# Smartbox.net
KiCad netlist of a schematic drawn in EAGLE
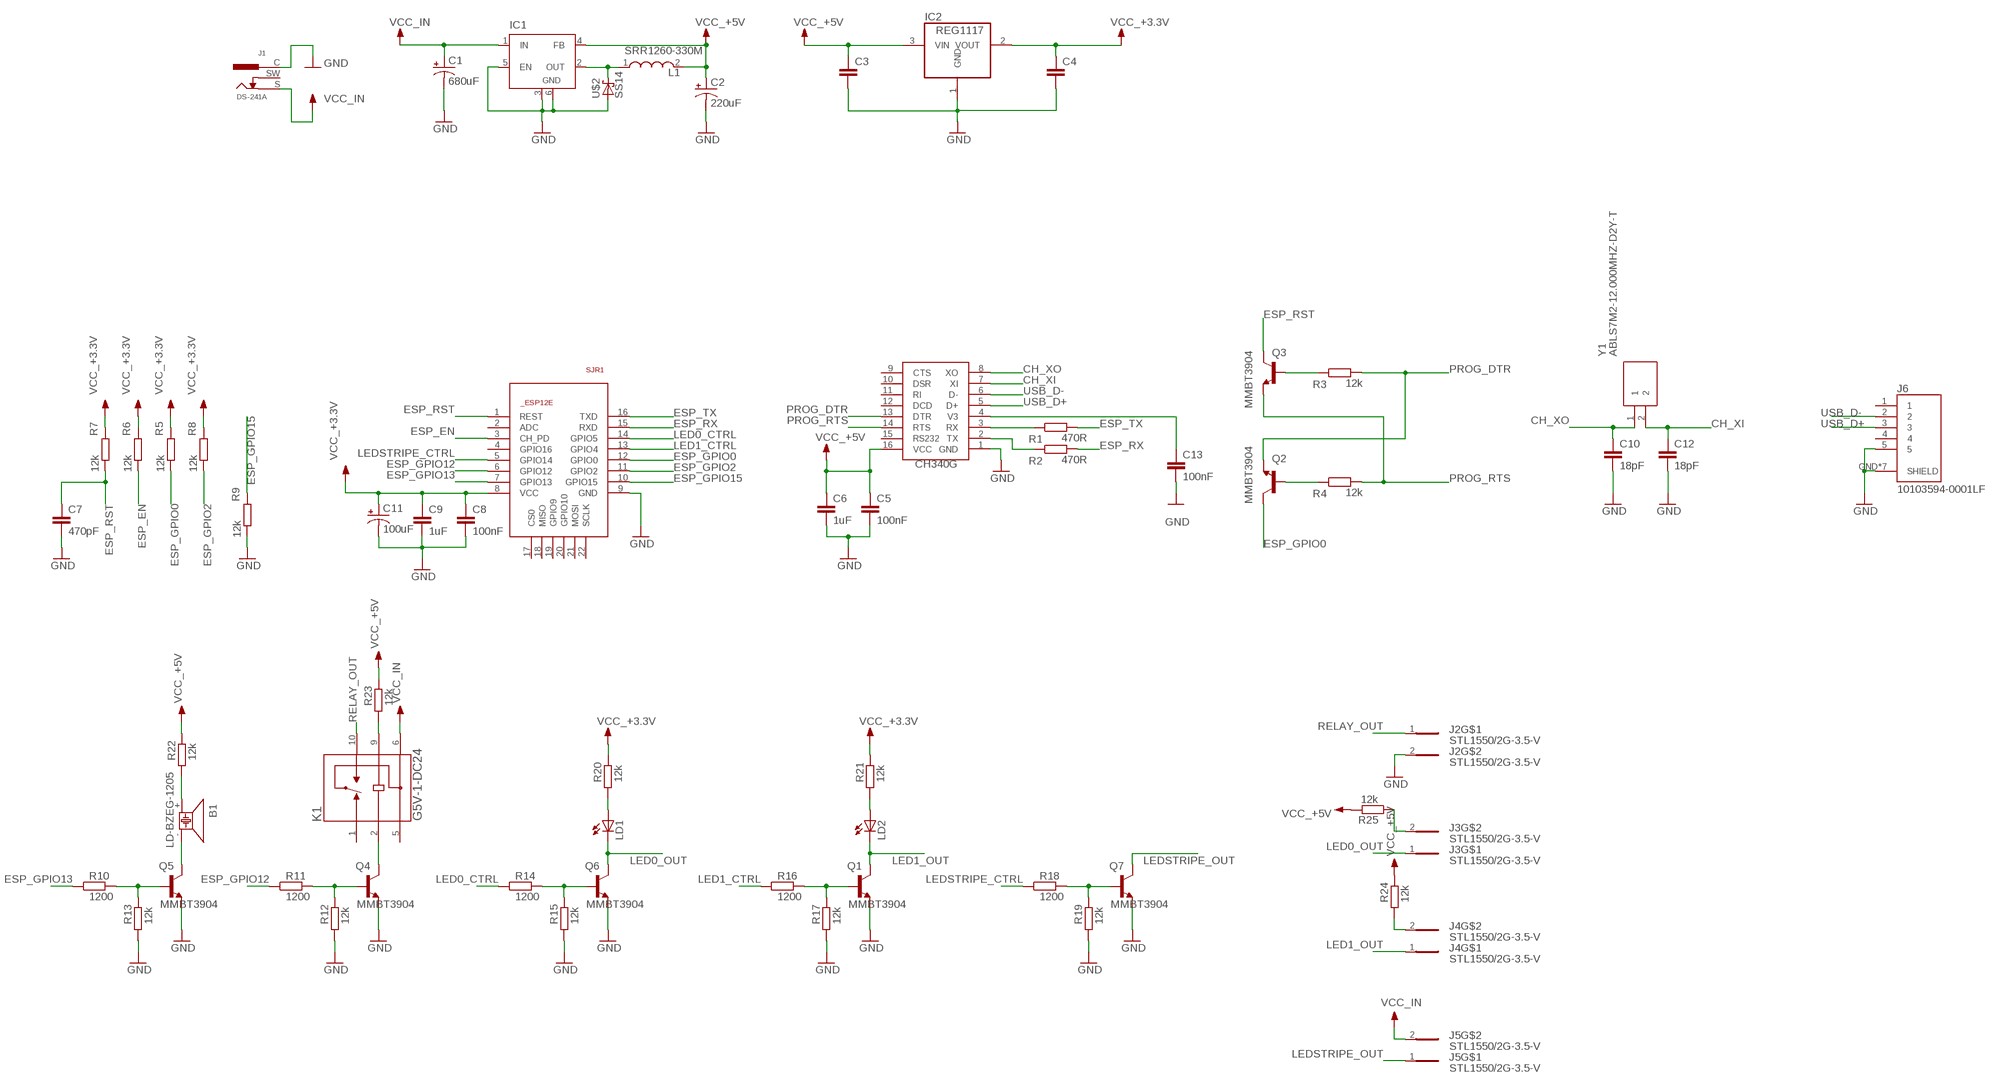
[diagram p0: schematic, sheet 1]

(export (version "E")
  (design (tool "Eeschema 10.0.6"))
  (components
    (comp (ref "B1")
      (value "LD-BZEG-1205")
      (footprint "eagle-import:LD-BZEG-12XX")
      (libsource (lib "eagle-import") (part "LD-BZEG-1205"))
    )
    (comp (ref "C1")
      (value "680uF")
      (footprint "eagle-import:PANASONIC_D")
      (libsource (lib "eagle-import") (part "100UF-POLAR-25V-20%(ELEC)"))
    )
    (comp (ref "C2")
      (value "220uF")
      (footprint "eagle-import:PANASONIC_D")
      (libsource (lib "eagle-import") (part "100UF-POLAR-25V-20%(ELEC)"))
    )
    (comp (ref "C3")
      (value "C-EUC0805")
      (footprint "eagle-import:C0805")
      (libsource (lib "eagle-import") (part "C-EUC0805"))
    )
    (comp (ref "C4")
      (value "C-EUC0805")
      (footprint "eagle-import:C0805")
      (libsource (lib "eagle-import") (part "C-EUC0805"))
    )
    (comp (ref "C5")
      (value "100nF")
      (footprint "eagle-import:C0805")
      (libsource (lib "eagle-import") (part "C-EUC0805"))
    )
    (comp (ref "C6")
      (value "1uF")
      (footprint "eagle-import:C0805")
      (libsource (lib "eagle-import") (part "C-EUC0805"))
    )
    (comp (ref "C7")
      (value "470pF")
      (footprint "eagle-import:C0805")
      (libsource (lib "eagle-import") (part "C-EUC0805"))
    )
    (comp (ref "C8")
      (value "100nF")
      (footprint "eagle-import:C0805")
      (libsource (lib "eagle-import") (part "C-EUC0805"))
    )
    (comp (ref "C9")
      (value "1uF")
      (footprint "eagle-import:C0805")
      (libsource (lib "eagle-import") (part "C-EUC0805"))
    )
    (comp (ref "C10")
      (value "18pF")
      (footprint "eagle-import:C0805")
      (libsource (lib "eagle-import") (part "C-EUC0805"))
    )
    (comp (ref "C11")
      (value "100uF")
      (footprint "eagle-import:PANASONIC_D")
      (libsource (lib "eagle-import") (part "100UF-POLAR-25V-20%(ELEC)"))
    )
    (comp (ref "C12")
      (value "18pF")
      (footprint "eagle-import:C0805")
      (libsource (lib "eagle-import") (part "C-EUC0805"))
    )
    (comp (ref "C13")
      (value "100nF")
      (footprint "eagle-import:C0805")
      (libsource (lib "eagle-import") (part "C-EUC0805"))
    )
    (comp (ref "IC1")
      (value "LM2596S")
      (footprint "eagle-import:TO263-5")
      (libsource (lib "eagle-import") (part "LM2596S"))
    )
    (comp (ref "IC2")
      (value "REG1117")
      (footprint "eagle-import:SOT223")
      (libsource (lib "eagle-import") (part "REG1117"))
    )
    (comp (ref "J1")
      (value "DS-241A")
      (footprint "eagle-import:DS-241")
      (libsource (lib "eagle-import") (part "DS-241A"))
    )
    (comp (ref "J2")
      (value "STL1550/2G-3.5-V")
      (footprint "eagle-import:STL1550_2G-3.5-V-GREEN")
      (libsource (lib "eagle-import") (part "STL1550/2G-3.5-V"))
    )
    (comp (ref "J3")
      (value "STL1550/2G-3.5-V")
      (footprint "eagle-import:STL1550_2G-3.5-V-GREEN")
      (libsource (lib "eagle-import") (part "STL1550/2G-3.5-V"))
    )
    (comp (ref "J4")
      (value "STL1550/2G-3.5-V")
      (footprint "eagle-import:STL1550_2G-3.5-V-GREEN")
      (libsource (lib "eagle-import") (part "STL1550/2G-3.5-V"))
    )
    (comp (ref "J5")
      (value "STL1550/2G-3.5-V")
      (footprint "eagle-import:STL1550_2G-3.5-V-GREEN")
      (libsource (lib "eagle-import") (part "STL1550/2G-3.5-V"))
    )
    (comp (ref "J6")
      (value "10103594-0001LF")
      (footprint "eagle-import:10103594-0001LF")
      (fields
        (field (name "DIGIKEY_PART_NUMBER") "609-4050-2-ND")
        (field (name "MANUFACTURER") "Amphenol ICC (FCI)")
        (field (name "CREATED_BY") "PCBLayout.com")
      )
      (libsource (lib "eagle-import") (part "10103594-0001LF"))
    )
    (comp (ref "K1")
      (value "G5V-1-DC24")
      (footprint "eagle-import:G5V-1-DC24")
      (fields
        (field (name "MANUFACTURER") "Omron Electronics Inc-EMC Div")
        (field (name "CREATED_BY") "  PCBLayout.com")
      )
      (libsource (lib "eagle-import") (part "G5V-1-DC24"))
    )
    (comp (ref "L1")
      (value "SRR1260-330M")
      (footprint "eagle-import:SRR1260-150M")
      (fields (field (name "MOUSER_PART_NUMBER") "652-SRR1260-330M"))
      (libsource (lib "eagle-import") (part "SRR1260-330M"))
    )
    (comp (ref "LD1")
      (value "LEDCHIPLED_0805")
      (footprint "eagle-import:CHIPLED_0805")
      (libsource (lib "eagle-import") (part "LEDCHIPLED_0805"))
    )
    (comp (ref "LD2")
      (value "LEDCHIPLED_0805")
      (footprint "eagle-import:CHIPLED_0805")
      (libsource (lib "eagle-import") (part "LEDCHIPLED_0805"))
    )
    (comp (ref "Q1")
      (value "MMBT3904")
      (footprint "eagle-import:SOT23")
      (fields
        (field (name "DIGIKEY_PART_NUMBER") "MMBT3904FSCT-ND")
        (field (name "MANUFACTURER") "ON Semiconductor")
        (field (name "CREATED_BY") "PCBLayout.com")
      )
      (libsource (lib "eagle-import") (part "MMBT3904"))
    )
    (comp (ref "Q2")
      (value "MMBT3904")
      (footprint "eagle-import:SOT23")
      (fields
        (field (name "DIGIKEY_PART_NUMBER") "MMBT3904FSCT-ND")
        (field (name "MANUFACTURER") "ON Semiconductor")
        (field (name "CREATED_BY") "PCBLayout.com")
      )
      (libsource (lib "eagle-import") (part "MMBT3904"))
    )
    (comp (ref "Q3")
      (value "MMBT3904")
      (footprint "eagle-import:SOT23")
      (fields
        (field (name "DIGIKEY_PART_NUMBER") "MMBT3904FSCT-ND")
        (field (name "MANUFACTURER") "ON Semiconductor")
        (field (name "CREATED_BY") "PCBLayout.com")
      )
      (libsource (lib "eagle-import") (part "MMBT3904"))
    )
    (comp (ref "Q4")
      (value "MMBT3904")
      (footprint "eagle-import:SOT23")
      (fields
        (field (name "DIGIKEY_PART_NUMBER") "MMBT3904FSCT-ND")
        (field (name "MANUFACTURER") "ON Semiconductor")
        (field (name "CREATED_BY") "PCBLayout.com")
      )
      (libsource (lib "eagle-import") (part "MMBT3904"))
    )
    (comp (ref "Q5")
      (value "MMBT3904")
      (footprint "eagle-import:SOT23")
      (fields
        (field (name "DIGIKEY_PART_NUMBER") "MMBT3904FSCT-ND")
        (field (name "MANUFACTURER") "ON Semiconductor")
        (field (name "CREATED_BY") "PCBLayout.com")
      )
      (libsource (lib "eagle-import") (part "MMBT3904"))
    )
    (comp (ref "Q6")
      (value "MMBT3904")
      (footprint "eagle-import:SOT23")
      (fields
        (field (name "DIGIKEY_PART_NUMBER") "MMBT3904FSCT-ND")
        (field (name "MANUFACTURER") "ON Semiconductor")
        (field (name "CREATED_BY") "PCBLayout.com")
      )
      (libsource (lib "eagle-import") (part "MMBT3904"))
    )
    (comp (ref "Q7")
      (value "MMBT3904")
      (footprint "eagle-import:SOT23")
      (fields
        (field (name "DIGIKEY_PART_NUMBER") "MMBT3904FSCT-ND")
        (field (name "MANUFACTURER") "ON Semiconductor")
        (field (name "CREATED_BY") "PCBLayout.com")
      )
      (libsource (lib "eagle-import") (part "MMBT3904"))
    )
    (comp (ref "R1")
      (value "470R")
      (footprint "eagle-import:R0805")
      (libsource (lib "eagle-import") (part "R-EU_R0805"))
    )
    (comp (ref "R2")
      (value "470R")
      (footprint "eagle-import:R0805")
      (libsource (lib "eagle-import") (part "R-EU_R0805"))
    )
    (comp (ref "R3")
      (value "12k")
      (footprint "eagle-import:R0805")
      (libsource (lib "eagle-import") (part "R-EU_R0805"))
    )
    (comp (ref "R4")
      (value "12k")
      (footprint "eagle-import:R0805")
      (libsource (lib "eagle-import") (part "R-EU_R0805"))
    )
    (comp (ref "R5")
      (value "12k")
      (footprint "eagle-import:R0805")
      (libsource (lib "eagle-import") (part "R-EU_R0805"))
    )
    (comp (ref "R6")
      (value "12k")
      (footprint "eagle-import:R0805")
      (libsource (lib "eagle-import") (part "R-EU_R0805"))
    )
    (comp (ref "R7")
      (value "12k")
      (footprint "eagle-import:R0805")
      (libsource (lib "eagle-import") (part "R-EU_R0805"))
    )
    (comp (ref "R8")
      (value "12k")
      (footprint "eagle-import:R0805")
      (libsource (lib "eagle-import") (part "R-EU_R0805"))
    )
    (comp (ref "R9")
      (value "12k")
      (footprint "eagle-import:R0805")
      (libsource (lib "eagle-import") (part "R-EU_R0805"))
    )
    (comp (ref "R10")
      (value "1200")
      (footprint "eagle-import:R0805")
      (libsource (lib "eagle-import") (part "R-EU_R0805"))
    )
    (comp (ref "R11")
      (value "1200")
      (footprint "eagle-import:R0805")
      (libsource (lib "eagle-import") (part "R-EU_R0805"))
    )
    (comp (ref "R12")
      (value "12k")
      (footprint "eagle-import:R0805")
      (libsource (lib "eagle-import") (part "R-EU_R0805"))
    )
    (comp (ref "R13")
      (value "12k")
      (footprint "eagle-import:R0805")
      (libsource (lib "eagle-import") (part "R-EU_R0805"))
    )
    (comp (ref "R14")
      (value "1200")
      (footprint "eagle-import:R0805")
      (libsource (lib "eagle-import") (part "R-EU_R0805"))
    )
    (comp (ref "R15")
      (value "12k")
      (footprint "eagle-import:R0805")
      (libsource (lib "eagle-import") (part "R-EU_R0805"))
    )
    (comp (ref "R16")
      (value "1200")
      (footprint "eagle-import:R0805")
      (libsource (lib "eagle-import") (part "R-EU_R0805"))
    )
    (comp (ref "R17")
      (value "12k")
      (footprint "eagle-import:R0805")
      (libsource (lib "eagle-import") (part "R-EU_R0805"))
    )
    (comp (ref "R18")
      (value "1200")
      (footprint "eagle-import:R0805")
      (libsource (lib "eagle-import") (part "R-EU_R0805"))
    )
    (comp (ref "R19")
      (value "12k")
      (footprint "eagle-import:R0805")
      (libsource (lib "eagle-import") (part "R-EU_R0805"))
    )
    (comp (ref "R20")
      (value "12k")
      (footprint "eagle-import:R0805")
      (libsource (lib "eagle-import") (part "R-EU_R0805"))
    )
    (comp (ref "R21")
      (value "12k")
      (footprint "eagle-import:R0805")
      (libsource (lib "eagle-import") (part "R-EU_R0805"))
    )
    (comp (ref "R22")
      (value "12k")
      (footprint "eagle-import:R0805")
      (libsource (lib "eagle-import") (part "R-EU_R0805"))
    )
    (comp (ref "R23")
      (value "12k")
      (footprint "eagle-import:R0805")
      (libsource (lib "eagle-import") (part "R-EU_R0805"))
    )
    (comp (ref "R24")
      (value "12k")
      (footprint "eagle-import:R0805")
      (libsource (lib "eagle-import") (part "R-EU_R0805"))
    )
    (comp (ref "R25")
      (value "12k")
      (footprint "eagle-import:R0805")
      (libsource (lib "eagle-import") (part "R-EU_R0805"))
    )
    (comp (ref "SJR1")
      (value "ESP8266-12EESP12E")
      (footprint "eagle-import:ESP8266-ESP12E")
      (libsource (lib "eagle-import") (part "ESP8266-12EESP12E"))
    )
    (comp (ref "U$2")
      (value "SS14")
      (footprint "eagle-import:DO-214AC")
      (fields (field (name "MF") "ON Semiconductor"))
      (libsource (lib "eagle-import") (part "SS14"))
    )
    (comp (ref "U$3")
      (value "CH340G")
      (footprint "eagle-import:SOIC16")
      (libsource (lib "eagle-import") (part "CH340G"))
    )
    (comp (ref "Y1")
      (value "ABLS7M2-12.000MHZ-D2Y-T")
      (footprint "eagle-import:ABLS7M216000MHZD2YT")
      (fields
        (field (name "MANUFACTURER_PART_NUMBER") "ABLS7M2-16.000MHZ-D2Y-T")
        (field (name "MOUSER_PART_NUMBER") "815-ABLS7M216MHZD2YT")
      )
      (libsource (lib "eagle-import") (part "ABLS7M2-16.000MHZ-D2Y-T"))
    )
  )
  (nets
    (net (code "1") (name "/CH_XI") (class "Default")
      (node (ref "C12") (pin "1") (pinfunction "1_1") (pintype "passive"))
      (node (ref "U$3") (pin "7") (pinfunction "XI_7") (pintype "bidirectional"))
      (node (ref "Y1") (pin "2") (pinfunction "2_2") (pintype "bidirectional"))
    )
    (net (code "2") (name "/CH_XO") (class "Default")
      (node (ref "C10") (pin "1") (pinfunction "1_1") (pintype "passive"))
      (node (ref "U$3") (pin "8") (pinfunction "XO_8") (pintype "bidirectional"))
      (node (ref "Y1") (pin "1") (pinfunction "1_1") (pintype "bidirectional"))
    )
    (net (code "3") (name "/ESP_EN") (class "Default")
      (node (ref "R6") (pin "2") (pinfunction "2_2") (pintype "passive"))
      (node (ref "SJR1") (pin "3") (pinfunction "CH_PD_3") (pintype "bidirectional"))
    )
    (net (code "4") (name "/ESP_GPIO0") (class "Default")
      (node (ref "Q2") (pin "3") (pinfunction "C_3") (pintype "passive"))
      (node (ref "R5") (pin "2") (pinfunction "2_2") (pintype "passive"))
      (node (ref "SJR1") (pin "12") (pinfunction "GPIO0_12") (pintype "bidirectional"))
    )
    (net (code "5") (name "/ESP_GPIO2") (class "Default")
      (node (ref "R8") (pin "2") (pinfunction "2_2") (pintype "passive"))
      (node (ref "SJR1") (pin "11") (pinfunction "GPIO2_11") (pintype "bidirectional"))
    )
    (net (code "6") (name "/ESP_GPIO12") (class "Default")
      (node (ref "R11") (pin "1") (pinfunction "1_1") (pintype "passive"))
      (node (ref "SJR1") (pin "6") (pinfunction "GPIO12_6") (pintype "bidirectional"))
    )
    (net (code "7") (name "/ESP_GPIO13") (class "Default")
      (node (ref "R10") (pin "1") (pinfunction "1_1") (pintype "passive"))
      (node (ref "SJR1") (pin "7") (pinfunction "GPIO13_7") (pintype "bidirectional"))
    )
    (net (code "8") (name "/ESP_GPIO15") (class "Default")
      (node (ref "R9") (pin "1") (pinfunction "1_1") (pintype "passive"))
      (node (ref "SJR1") (pin "10") (pinfunction "GPIO15_10") (pintype "bidirectional"))
    )
    (net (code "9") (name "/ESP_RST") (class "Default")
      (node (ref "C7") (pin "1") (pinfunction "1_1") (pintype "passive"))
      (node (ref "Q3") (pin "3") (pinfunction "C_3") (pintype "passive"))
      (node (ref "R7") (pin "2") (pinfunction "2_2") (pintype "passive"))
      (node (ref "SJR1") (pin "1") (pinfunction "REST_1") (pintype "bidirectional"))
    )
    (net (code "10") (name "/ESP_RX") (class "Default")
      (node (ref "R2") (pin "2") (pinfunction "2_2") (pintype "passive"))
      (node (ref "SJR1") (pin "15") (pinfunction "RXD_15") (pintype "bidirectional"))
    )
    (net (code "11") (name "/ESP_TX") (class "Default")
      (node (ref "R1") (pin "2") (pinfunction "2_2") (pintype "passive"))
      (node (ref "SJR1") (pin "16") (pinfunction "TXD_16") (pintype "bidirectional"))
    )
    (net (code "12") (name "/LED0_CTRL") (class "Default")
      (node (ref "R14") (pin "1") (pinfunction "1_1") (pintype "passive"))
      (node (ref "SJR1") (pin "14") (pinfunction "GPIO5_14") (pintype "bidirectional"))
    )
    (net (code "13") (name "/LED0_OUT") (class "Default")
      (node (ref "J3") (pin "1") (pinfunction "1_1") (pintype "passive"))
      (node (ref "LD1") (pin "C") (pinfunction "C_C") (pintype "passive"))
      (node (ref "Q6") (pin "3") (pinfunction "C_3") (pintype "passive"))
    )
    (net (code "14") (name "/LED1_CTRL") (class "Default")
      (node (ref "R16") (pin "1") (pinfunction "1_1") (pintype "passive"))
      (node (ref "SJR1") (pin "13") (pinfunction "GPIO4_13") (pintype "bidirectional"))
    )
    (net (code "15") (name "/LED1_OUT") (class "Default")
      (node (ref "J4") (pin "1") (pinfunction "1_1") (pintype "passive"))
      (node (ref "LD2") (pin "C") (pinfunction "C_C") (pintype "passive"))
      (node (ref "Q1") (pin "3") (pinfunction "C_3") (pintype "passive"))
    )
    (net (code "16") (name "/LEDSTRIPE_CTRL") (class "Default")
      (node (ref "R18") (pin "1") (pinfunction "1_1") (pintype "passive"))
      (node (ref "SJR1") (pin "5") (pinfunction "GPIO14_5") (pintype "bidirectional"))
    )
    (net (code "17") (name "/LEDSTRIPE_OUT") (class "Default")
      (node (ref "J5") (pin "1") (pinfunction "1_1") (pintype "passive"))
      (node (ref "Q7") (pin "3") (pinfunction "C_3") (pintype "passive"))
    )
    (net (code "18") (name "/PROG_DTR") (class "Default")
      (node (ref "Q2") (pin "2") (pinfunction "E_2") (pintype "passive"))
      (node (ref "R3") (pin "2") (pinfunction "2_2") (pintype "passive"))
      (node (ref "U$3") (pin "13") (pinfunction "DTR_13") (pintype "bidirectional"))
    )
    (net (code "19") (name "/PROG_RTS") (class "Default")
      (node (ref "Q3") (pin "2") (pinfunction "E_2") (pintype "passive"))
      (node (ref "R4") (pin "2") (pinfunction "2_2") (pintype "passive"))
      (node (ref "U$3") (pin "14") (pinfunction "RTS_14") (pintype "bidirectional"))
    )
    (net (code "20") (name "/RELAY_OUT") (class "Default")
      (node (ref "J2") (pin "1") (pinfunction "1_1") (pintype "passive"))
      (node (ref "K1") (pin "10") (pinfunction "10_10") (pintype "passive"))
    )
    (net (code "21") (name "/USB_D+") (class "Default")
      (node (ref "J6") (pin "3") (pinfunction "3_3") (pintype "passive"))
      (node (ref "U$3") (pin "5") (pinfunction "D+_5") (pintype "bidirectional"))
    )
    (net (code "22") (name "/USB_D-") (class "Default")
      (node (ref "J6") (pin "2") (pinfunction "2_2") (pintype "passive"))
      (node (ref "U$3") (pin "6") (pinfunction "D-_6") (pintype "bidirectional"))
    )
    (net (code "23") (name "GND") (class "Default")
      (node (ref "C1") (pin "-") (pinfunction "-_-") (pintype "passive"))
      (node (ref "C10") (pin "2") (pinfunction "2_2") (pintype "passive"))
      (node (ref "C11") (pin "-") (pinfunction "-_-") (pintype "passive"))
      (node (ref "C12") (pin "2") (pinfunction "2_2") (pintype "passive"))
      (node (ref "C13") (pin "1") (pinfunction "1_1") (pintype "passive"))
      (node (ref "C2") (pin "-") (pinfunction "-_-") (pintype "passive"))
      (node (ref "C3") (pin "2") (pinfunction "2_2") (pintype "passive"))
      (node (ref "C4") (pin "2") (pinfunction "2_2") (pintype "passive"))
      (node (ref "C5") (pin "2") (pinfunction "2_2") (pintype "passive"))
      (node (ref "C6") (pin "2") (pinfunction "2_2") (pintype "passive"))
      (node (ref "C7") (pin "2") (pinfunction "2_2") (pintype "passive"))
      (node (ref "C8") (pin "2") (pinfunction "2_2") (pintype "passive"))
      (node (ref "C9") (pin "2") (pinfunction "2_2") (pintype "passive"))
      (node (ref "IC1") (pin "3") (pinfunction "GND_3") (pintype "power_in"))
      (node (ref "IC1") (pin "5") (pinfunction "EN_5") (pintype "input"))
      (node (ref "IC1") (pin "6") (pinfunction "GND_6") (pintype "power_in"))
      (node (ref "IC2") (pin "1") (pinfunction "GND_1") (pintype "power_in"))
      (node (ref "J1") (pin "C") (pinfunction "C_C") (pintype "passive"))
      (node (ref "J2") (pin "2") (pinfunction "1_2") (pintype "passive"))
      (node (ref "J6") (pin "5") (pinfunction "5_5") (pintype "passive"))
      (node (ref "J6") (pin "GND") (pinfunction "SHIELD_GND") (pintype "passive"))
      (node (ref "J6") (pin "GND$1") (pinfunction "SHIELD_GND$1") (pintype "passive"))
      (node (ref "J6") (pin "GND$2") (pinfunction "SHIELD_GND$2") (pintype "passive"))
      (node (ref "J6") (pin "S1") (pinfunction "SHIELD_S1") (pintype "passive"))
      (node (ref "J6") (pin "S2") (pinfunction "SHIELD_S2") (pintype "passive"))
      (node (ref "J6") (pin "S3") (pinfunction "SHIELD_S3") (pintype "passive"))
      (node (ref "J6") (pin "S4") (pinfunction "SHIELD_S4") (pintype "passive"))
      (node (ref "Q1") (pin "2") (pinfunction "E_2") (pintype "passive"))
      (node (ref "Q4") (pin "2") (pinfunction "E_2") (pintype "passive"))
      (node (ref "Q5") (pin "2") (pinfunction "E_2") (pintype "passive"))
      (node (ref "Q6") (pin "2") (pinfunction "E_2") (pintype "passive"))
      (node (ref "Q7") (pin "2") (pinfunction "E_2") (pintype "passive"))
      (node (ref "R12") (pin "1") (pinfunction "1_1") (pintype "passive"))
      (node (ref "R13") (pin "1") (pinfunction "1_1") (pintype "passive"))
      (node (ref "R15") (pin "1") (pinfunction "1_1") (pintype "passive"))
      (node (ref "R17") (pin "1") (pinfunction "1_1") (pintype "passive"))
      (node (ref "R19") (pin "1") (pinfunction "1_1") (pintype "passive"))
      (node (ref "R9") (pin "2") (pinfunction "2_2") (pintype "passive"))
      (node (ref "SJR1") (pin "9") (pinfunction "GND_9") (pintype "bidirectional"))
      (node (ref "U$2") (pin "A") (pinfunction "A_A") (pintype "passive"))
      (node (ref "U$3") (pin "1") (pinfunction "GND_1") (pintype "bidirectional"))
    )
    (net (code "24") (name "Net-(B1-Pad+)") (class "Default")
      (node (ref "B1") (pin "+") (pinfunction "+_+") (pintype "passive"))
      (node (ref "R22") (pin "1") (pinfunction "1_1") (pintype "passive"))
    )
    (net (code "25") (name "Net-(IC1-OUT)") (class "Default")
      (node (ref "IC1") (pin "2") (pinfunction "OUT_2") (pintype "output"))
      (node (ref "L1") (pin "1") (pinfunction "1_1") (pintype "bidirectional"))
      (node (ref "U$2") (pin "C") (pinfunction "C_C") (pintype "passive"))
    )
    (net (code "26") (name "Net-(J3B-1)") (class "Default")
      (node (ref "J3") (pin "2") (pinfunction "1_2") (pintype "passive"))
      (node (ref "R25") (pin "1") (pinfunction "1_1") (pintype "passive"))
    )
    (net (code "27") (name "Net-(J4B-1)") (class "Default")
      (node (ref "J4") (pin "2") (pinfunction "1_2") (pintype "passive"))
      (node (ref "R24") (pin "1") (pinfunction "1_1") (pintype "passive"))
    )
    (net (code "28") (name "Net-(K1-Pad9)") (class "Default")
      (node (ref "K1") (pin "9") (pinfunction "9_9") (pintype "passive"))
      (node (ref "R23") (pin "1") (pinfunction "1_1") (pintype "passive"))
    )
    (net (code "29") (name "Net-(LD1-PadA)") (class "Default")
      (node (ref "LD1") (pin "A") (pinfunction "A_A") (pintype "passive"))
      (node (ref "R20") (pin "1") (pinfunction "1_1") (pintype "passive"))
    )
    (net (code "30") (name "Net-(LD2-PadA)") (class "Default")
      (node (ref "LD2") (pin "A") (pinfunction "A_A") (pintype "passive"))
      (node (ref "R21") (pin "1") (pinfunction "1_1") (pintype "passive"))
    )
    (net (code "31") (name "Net-(Q1-B)") (class "Default")
      (node (ref "Q1") (pin "1") (pinfunction "B_1") (pintype "passive"))
      (node (ref "R16") (pin "2") (pinfunction "2_2") (pintype "passive"))
      (node (ref "R17") (pin "2") (pinfunction "2_2") (pintype "passive"))
    )
    (net (code "32") (name "Net-(Q2-B)") (class "Default")
      (node (ref "Q2") (pin "1") (pinfunction "B_1") (pintype "passive"))
      (node (ref "R4") (pin "1") (pinfunction "1_1") (pintype "passive"))
    )
    (net (code "33") (name "Net-(Q3-B)") (class "Default")
      (node (ref "Q3") (pin "1") (pinfunction "B_1") (pintype "passive"))
      (node (ref "R3") (pin "1") (pinfunction "1_1") (pintype "passive"))
    )
    (net (code "34") (name "Net-(Q4-B)") (class "Default")
      (node (ref "Q4") (pin "1") (pinfunction "B_1") (pintype "passive"))
      (node (ref "R11") (pin "2") (pinfunction "2_2") (pintype "passive"))
      (node (ref "R12") (pin "2") (pinfunction "2_2") (pintype "passive"))
    )
    (net (code "35") (name "Net-(Q4-C)") (class "Default")
      (node (ref "K1") (pin "2") (pinfunction "2_2") (pintype "passive"))
      (node (ref "Q4") (pin "3") (pinfunction "C_3") (pintype "passive"))
    )
    (net (code "36") (name "Net-(Q5-B)") (class "Default")
      (node (ref "Q5") (pin "1") (pinfunction "B_1") (pintype "passive"))
      (node (ref "R10") (pin "2") (pinfunction "2_2") (pintype "passive"))
      (node (ref "R13") (pin "2") (pinfunction "2_2") (pintype "passive"))
    )
    (net (code "37") (name "Net-(Q5-C)") (class "Default")
      (node (ref "B1") (pin "-") (pinfunction "-_-") (pintype "passive"))
      (node (ref "Q5") (pin "3") (pinfunction "C_3") (pintype "passive"))
    )
    (net (code "38") (name "Net-(Q6-B)") (class "Default")
      (node (ref "Q6") (pin "1") (pinfunction "B_1") (pintype "passive"))
      (node (ref "R14") (pin "2") (pinfunction "2_2") (pintype "passive"))
      (node (ref "R15") (pin "2") (pinfunction "2_2") (pintype "passive"))
    )
    (net (code "39") (name "Net-(Q7-B)") (class "Default")
      (node (ref "Q7") (pin "1") (pinfunction "B_1") (pintype "passive"))
      (node (ref "R18") (pin "2") (pinfunction "2_2") (pintype "passive"))
      (node (ref "R19") (pin "2") (pinfunction "2_2") (pintype "passive"))
    )
    (net (code "40") (name "Net-(U$3-RX)") (class "Default")
      (node (ref "R1") (pin "1") (pinfunction "1_1") (pintype "passive"))
      (node (ref "U$3") (pin "3") (pinfunction "RX_3") (pintype "bidirectional"))
    )
    (net (code "41") (name "Net-(U$3-TX)") (class "Default")
      (node (ref "R2") (pin "1") (pinfunction "1_1") (pintype "passive"))
      (node (ref "U$3") (pin "2") (pinfunction "TX_2") (pintype "bidirectional"))
    )
    (net (code "42") (name "Net-(U$3-V3)") (class "Default")
      (node (ref "C13") (pin "2") (pinfunction "2_2") (pintype "passive"))
      (node (ref "U$3") (pin "4") (pinfunction "V3_4") (pintype "bidirectional"))
    )
    (net (code "43") (name "VCC_+3.3V") (class "Default")
      (node (ref "C11") (pin "+") (pinfunction "+_+") (pintype "passive"))
      (node (ref "C4") (pin "1") (pinfunction "1_1") (pintype "passive"))
      (node (ref "C8") (pin "1") (pinfunction "1_1") (pintype "passive"))
      (node (ref "C9") (pin "1") (pinfunction "1_1") (pintype "passive"))
      (node (ref "IC2") (pin "2") (pinfunction "VOUT_2") (pintype "output"))
      (node (ref "R20") (pin "2") (pinfunction "2_2") (pintype "passive"))
      (node (ref "R21") (pin "2") (pinfunction "2_2") (pintype "passive"))
      (node (ref "R5") (pin "1") (pinfunction "1_1") (pintype "passive"))
      (node (ref "R6") (pin "1") (pinfunction "1_1") (pintype "passive"))
      (node (ref "R7") (pin "1") (pinfunction "1_1") (pintype "passive"))
      (node (ref "R8") (pin "1") (pinfunction "1_1") (pintype "passive"))
      (node (ref "SJR1") (pin "8") (pinfunction "VCC_8") (pintype "bidirectional"))
    )
    (net (code "44") (name "VCC_+5V") (class "Default")
      (node (ref "C2") (pin "+") (pinfunction "+_+") (pintype "passive"))
      (node (ref "C3") (pin "1") (pinfunction "1_1") (pintype "passive"))
      (node (ref "C5") (pin "1") (pinfunction "1_1") (pintype "passive"))
      (node (ref "C6") (pin "1") (pinfunction "1_1") (pintype "passive"))
      (node (ref "IC1") (pin "4") (pinfunction "FB_4") (pintype "input"))
      (node (ref "IC2") (pin "3") (pinfunction "VIN_3") (pintype "input"))
      (node (ref "L1") (pin "2") (pinfunction "2_2") (pintype "bidirectional"))
      (node (ref "R22") (pin "2") (pinfunction "2_2") (pintype "passive"))
      (node (ref "R23") (pin "2") (pinfunction "2_2") (pintype "passive"))
      (node (ref "R24") (pin "2") (pinfunction "2_2") (pintype "passive"))
      (node (ref "R25") (pin "2") (pinfunction "2_2") (pintype "passive"))
      (node (ref "U$3") (pin "16") (pinfunction "VCC_16") (pintype "bidirectional"))
    )
    (net (code "45") (name "VCC_IN") (class "Default")
      (node (ref "C1") (pin "+") (pinfunction "+_+") (pintype "passive"))
      (node (ref "IC1") (pin "1") (pinfunction "IN_1") (pintype "input"))
      (node (ref "J1") (pin "S") (pinfunction "S_S") (pintype "passive"))
      (node (ref "J5") (pin "2") (pinfunction "1_2") (pintype "passive"))
      (node (ref "K1") (pin "6") (pinfunction "6_6") (pintype "passive"))
    )
    (net (code "46") (name "unconnected-(J1-PadSW)") (class "Default")
      (node (ref "J1") (pin "SW") (pinfunction "SW_SW") (pintype "passive"))
    )
    (net (code "47") (name "unconnected-(J6-Pad1)") (class "Default")
      (node (ref "J6") (pin "1") (pinfunction "1_1") (pintype "passive"))
    )
    (net (code "48") (name "unconnected-(J6-Pad4)") (class "Default")
      (node (ref "J6") (pin "4") (pinfunction "4_4") (pintype "passive"))
    )
    (net (code "49") (name "unconnected-(K1-Pad1)") (class "Default")
      (node (ref "K1") (pin "1") (pinfunction "1_1") (pintype "passive"))
    )
    (net (code "50") (name "unconnected-(K1-Pad5)") (class "Default")
      (node (ref "K1") (pin "5") (pinfunction "5_5") (pintype "passive"))
    )
    (net (code "51") (name "unconnected-(SJR1-ADC-Pad2)") (class "Default")
      (node (ref "SJR1") (pin "2") (pinfunction "ADC_2") (pintype "bidirectional"))
    )
    (net (code "52") (name "unconnected-(SJR1-CS0-Pad17)") (class "Default")
      (node (ref "SJR1") (pin "17") (pinfunction "CS0_17") (pintype "bidirectional"))
    )
    (net (code "53") (name "unconnected-(SJR1-GPIO9-Pad19)") (class "Default")
      (node (ref "SJR1") (pin "19") (pinfunction "GPIO9_19") (pintype "bidirectional"))
    )
    (net (code "54") (name "unconnected-(SJR1-GPIO10-Pad20)") (class "Default")
      (node (ref "SJR1") (pin "20") (pinfunction "GPIO10_20") (pintype "bidirectional"))
    )
    (net (code "55") (name "unconnected-(SJR1-GPIO16-Pad4)") (class "Default")
      (node (ref "SJR1") (pin "4") (pinfunction "GPIO16_4") (pintype "bidirectional"))
    )
    (net (code "56") (name "unconnected-(SJR1-MISO-Pad18)") (class "Default")
      (node (ref "SJR1") (pin "18") (pinfunction "MISO_18") (pintype "bidirectional"))
    )
    (net (code "57") (name "unconnected-(SJR1-MOSI-Pad21)") (class "Default")
      (node (ref "SJR1") (pin "21") (pinfunction "MOSI_21") (pintype "bidirectional"))
    )
    (net (code "58") (name "unconnected-(SJR1-SCLK-Pad22)") (class "Default")
      (node (ref "SJR1") (pin "22") (pinfunction "SCLK_22") (pintype "bidirectional"))
    )
    (net (code "59") (name "unconnected-(U$3-CTS-Pad9)") (class "Default")
      (node (ref "U$3") (pin "9") (pinfunction "CTS_9") (pintype "bidirectional"))
    )
    (net (code "60") (name "unconnected-(U$3-DCD-Pad12)") (class "Default")
      (node (ref "U$3") (pin "12") (pinfunction "DCD_12") (pintype "bidirectional"))
    )
    (net (code "61") (name "unconnected-(U$3-DSR-Pad10)") (class "Default")
      (node (ref "U$3") (pin "10") (pinfunction "DSR_10") (pintype "bidirectional"))
    )
    (net (code "62") (name "unconnected-(U$3-RI-Pad11)") (class "Default")
      (node (ref "U$3") (pin "11") (pinfunction "RI_11") (pintype "bidirectional"))
    )
    (net (code "63") (name "unconnected-(U$3-RS232-Pad15)") (class "Default")
      (node (ref "U$3") (pin "15") (pinfunction "RS232_15") (pintype "bidirectional"))
    )
  )
)
